# CtDPS_Stage.net
KiCad netlist of a schematic drawn in Altium Designer
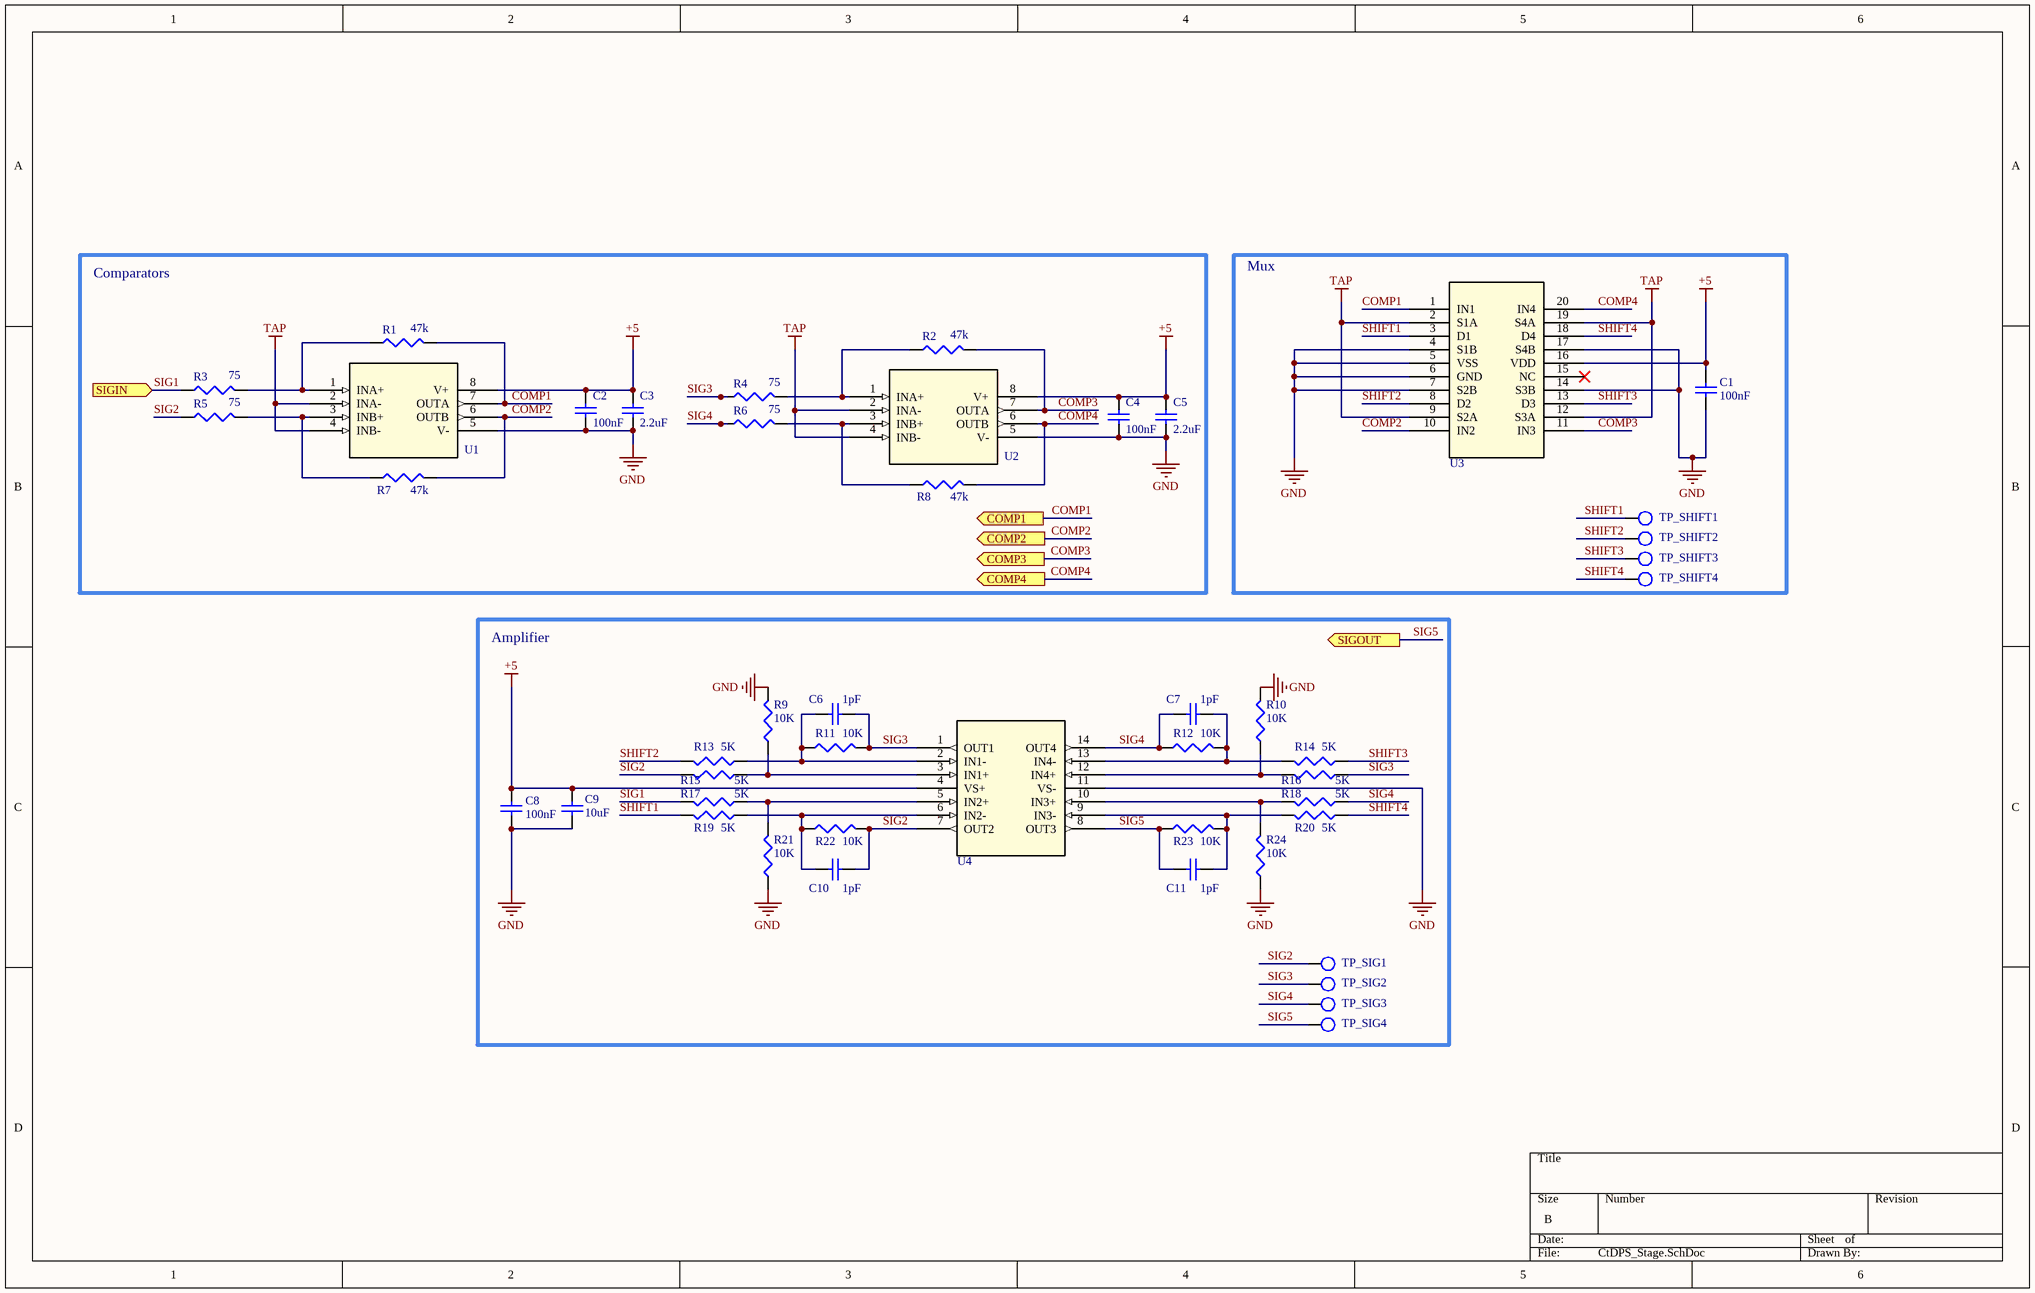
[diagram p0: CtDPS_Stage.SchDoc]

(export (version "E")
  (design (tool "Eeschema 10.0.6"))
  (components
    (comp (ref "C1")
      (value "100nF")
      (footprint "C_0402")
      (fields (field (name "LCSC PART #") "C1525"))
      (libsource (lib "ctdsp") (part "C_0402"))
    )
    (comp (ref "C2")
      (value "100nF")
      (footprint "C_0402")
      (fields (field (name "LCSC PART #") "C1525"))
      (libsource (lib "ctdsp") (part "C_0402"))
    )
    (comp (ref "C3")
      (value "2.2uF")
      (footprint "C_0402")
      (fields (field (name "LCSC PART #") "C12530"))
      (libsource (lib "ctdsp") (part "C_0402"))
    )
    (comp (ref "C4")
      (value "100nF")
      (footprint "C_0402")
      (fields (field (name "LCSC PART #") "C1525"))
      (libsource (lib "ctdsp") (part "C_0402"))
    )
    (comp (ref "C5")
      (value "2.2uF")
      (footprint "C_0402")
      (fields (field (name "LCSC PART #") "C12530"))
      (libsource (lib "ctdsp") (part "C_0402"))
    )
    (comp (ref "C6")
      (value "1pF")
      (footprint "C_0402")
      (fields (field (name "LCSC PART #") "C1550"))
      (libsource (lib "ctdsp") (part "C_0402"))
    )
    (comp (ref "C7")
      (value "1pF")
      (footprint "C_0402")
      (fields (field (name "LCSC PART #") "C1550"))
      (libsource (lib "ctdsp") (part "C_0402"))
    )
    (comp (ref "C8")
      (value "100nF")
      (footprint "C_0402")
      (fields (field (name "LCSC PART #") "C1525"))
      (libsource (lib "ctdsp") (part "C_0402"))
    )
    (comp (ref "C9")
      (value "10uF")
      (footprint "C_0402")
      (fields (field (name "LCSC PART #") "C15525"))
      (libsource (lib "ctdsp") (part "C_0402"))
    )
    (comp (ref "C10")
      (value "1pF")
      (footprint "C_0402")
      (fields (field (name "LCSC PART #") "C1550"))
      (libsource (lib "ctdsp") (part "C_0402"))
    )
    (comp (ref "C11")
      (value "1pF")
      (footprint "C_0402")
      (fields (field (name "LCSC PART #") "C1550"))
      (libsource (lib "ctdsp") (part "C_0402"))
    )
    (comp (ref "R1")
      (value "47k")
      (footprint "RES_0603")
      (fields (field (name "LCSC PART #") "C25819"))
      (libsource (lib "ctdsp") (part "RES_0603"))
    )
    (comp (ref "R2")
      (value "47k")
      (footprint "RES_0603")
      (fields (field (name "LCSC PART #") "C25819"))
      (libsource (lib "ctdsp") (part "RES_0603"))
    )
    (comp (ref "R3")
      (value "75")
      (footprint "RES_0603")
      (fields (field (name "LCSC PART #") "C4275"))
      (libsource (lib "ctdsp") (part "RES_0603"))
    )
    (comp (ref "R4")
      (value "75")
      (footprint "RES_0603")
      (fields (field (name "LCSC PART #") "C4275"))
      (libsource (lib "ctdsp") (part "RES_0603"))
    )
    (comp (ref "R5")
      (value "75")
      (footprint "RES_0603")
      (fields (field (name "LCSC PART #") "C4275"))
      (libsource (lib "ctdsp") (part "RES_0603"))
    )
    (comp (ref "R6")
      (value "75")
      (footprint "RES_0603")
      (fields (field (name "LCSC PART #") "C4275"))
      (libsource (lib "ctdsp") (part "RES_0603"))
    )
    (comp (ref "R7")
      (value "47k")
      (footprint "RES_0603")
      (fields (field (name "LCSC PART #") "C25819"))
      (libsource (lib "ctdsp") (part "RES_0603"))
    )
    (comp (ref "R8")
      (value "47k")
      (footprint "RES_0603")
      (fields (field (name "LCSC PART #") "C25819"))
      (libsource (lib "ctdsp") (part "RES_0603"))
    )
    (comp (ref "R9")
      (value "10K")
      (footprint "RES_0402")
      (fields (field (name "LCSC PART #") "C25744"))
      (libsource (lib "ctdsp") (part "RES_0402"))
    )
    (comp (ref "R10")
      (value "10K")
      (footprint "RES_0402")
      (fields (field (name "LCSC PART #") "C25744"))
      (libsource (lib "ctdsp") (part "RES_0402"))
    )
    (comp (ref "R11")
      (value "10K")
      (footprint "RES_0402")
      (fields (field (name "LCSC PART #") "C25744"))
      (libsource (lib "ctdsp") (part "RES_0402"))
    )
    (comp (ref "R12")
      (value "10K")
      (footprint "RES_0402")
      (fields (field (name "LCSC PART #") "C25744"))
      (libsource (lib "ctdsp") (part "RES_0402"))
    )
    (comp (ref "R13")
      (value "5K")
      (footprint "RES_0402")
      (fields (field (name "LCSC PART #") "C5948099"))
      (libsource (lib "ctdsp") (part "RES_0402"))
    )
    (comp (ref "R14")
      (value "5K")
      (footprint "RES_0402")
      (fields (field (name "LCSC PART #") "C5948099"))
      (libsource (lib "ctdsp") (part "RES_0402"))
    )
    (comp (ref "R15")
      (value "5K")
      (footprint "RES_0402")
      (fields (field (name "LCSC PART #") "C5948099"))
      (libsource (lib "ctdsp") (part "RES_0402"))
    )
    (comp (ref "R16")
      (value "5K")
      (footprint "RES_0402")
      (fields (field (name "LCSC PART #") "C5948099"))
      (libsource (lib "ctdsp") (part "RES_0402"))
    )
    (comp (ref "R17")
      (value "5K")
      (footprint "RES_0402")
      (fields (field (name "LCSC PART #") "C5948099"))
      (libsource (lib "ctdsp") (part "RES_0402"))
    )
    (comp (ref "R18")
      (value "5K")
      (footprint "RES_0402")
      (fields (field (name "LCSC PART #") "C5948099"))
      (libsource (lib "ctdsp") (part "RES_0402"))
    )
    (comp (ref "R19")
      (value "5K")
      (footprint "RES_0402")
      (fields (field (name "LCSC PART #") "C5948099"))
      (libsource (lib "ctdsp") (part "RES_0402"))
    )
    (comp (ref "R20")
      (value "5K")
      (footprint "RES_0402")
      (fields (field (name "LCSC PART #") "C5948099"))
      (libsource (lib "ctdsp") (part "RES_0402"))
    )
    (comp (ref "R21")
      (value "10K")
      (footprint "RES_0402")
      (fields (field (name "LCSC PART #") "C25744"))
      (libsource (lib "ctdsp") (part "RES_0402"))
    )
    (comp (ref "R22")
      (value "10K")
      (footprint "RES_0402")
      (fields (field (name "LCSC PART #") "C25744"))
      (libsource (lib "ctdsp") (part "RES_0402"))
    )
    (comp (ref "R23")
      (value "10K")
      (footprint "RES_0402")
      (fields (field (name "LCSC PART #") "C25744"))
      (libsource (lib "ctdsp") (part "RES_0402"))
    )
    (comp (ref "R24")
      (value "10K")
      (footprint "RES_0402")
      (fields (field (name "LCSC PART #") "C25744"))
      (libsource (lib "ctdsp") (part "RES_0402"))
    )
    (comp (ref "TP_SHIFT1")
      (value "TESTPOINT")
      (footprint "TESTPOINT")
      (libsource (lib "ctdsp") (part "TESTPOINT"))
    )
    (comp (ref "TP_SHIFT2")
      (value "TESTPOINT")
      (footprint "TESTPOINT")
      (libsource (lib "ctdsp") (part "TESTPOINT"))
    )
    (comp (ref "TP_SHIFT3")
      (value "TESTPOINT")
      (footprint "TESTPOINT")
      (libsource (lib "ctdsp") (part "TESTPOINT"))
    )
    (comp (ref "TP_SHIFT4")
      (value "TESTPOINT")
      (footprint "TESTPOINT")
      (libsource (lib "ctdsp") (part "TESTPOINT"))
    )
    (comp (ref "TP_SIG1")
      (value "TESTPOINT")
      (footprint "TESTPOINT")
      (libsource (lib "ctdsp") (part "TESTPOINT"))
    )
    (comp (ref "TP_SIG2")
      (value "TESTPOINT")
      (footprint "TESTPOINT")
      (libsource (lib "ctdsp") (part "TESTPOINT"))
    )
    (comp (ref "TP_SIG3")
      (value "TESTPOINT")
      (footprint "TESTPOINT")
      (libsource (lib "ctdsp") (part "TESTPOINT"))
    )
    (comp (ref "TP_SIG4")
      (value "TESTPOINT")
      (footprint "TESTPOINT")
      (libsource (lib "ctdsp") (part "TESTPOINT"))
    )
    (comp (ref "U1")
      (value "TLV3502AIDR")
      (footprint "TLV3502AIDR")
      (description "Dual 4.5ns Push-pull Rail-to-Rail Input, Rail-to-Rail Output TTL Comparators")
      (fields (field (name "LCSC PART #") "C131165"))
      (libsource (lib "ctdsp") (part "TLV3502AIDR"))
    )
    (comp (ref "U2")
      (value "TLV3502AIDR")
      (footprint "TLV3502AIDR")
      (description "Dual 4.5ns Push-pull Rail-to-Rail Input, Rail-to-Rail Output TTL Comparators")
      (fields (field (name "LCSC PART #") "C131165"))
      (libsource (lib "ctdsp") (part "TLV3502AIDR"))
    )
    (comp (ref "U3")
      (value "ADG734BRUZ-REEL")
      (footprint "ADG734BRUZ-REEL")
      (fields (field (name "LCSC PART #") "C579105"))
      (libsource (lib "ctdsp") (part "ADG734BRUZ-REEL"))
    )
    (comp (ref "U4")
      (value "ADA4891-4ARZ-R7")
      (footprint "ADA4891-4ARZ-R7")
      (description "Quad Rail-to-Rail Op-Amp, 240 MHz, 170 V/µs, SOT-23-5")
      (fields (field (name "LCSC PART #") "C654290"))
      (libsource (lib "ctdsp") (part "ADA4891-4ARZ-R7"))
    )
  )
  (nets
    (net (code "1") (name "+5") (class "Default")
      (node (ref "C1") (pin "1") (pinfunction "1_1") (pintype "passive"))
      (node (ref "C2") (pin "1") (pinfunction "1_1") (pintype "passive"))
      (node (ref "C3") (pin "2") (pinfunction "2_2") (pintype "passive"))
      (node (ref "C4") (pin "1") (pinfunction "1_1") (pintype "passive"))
      (node (ref "C5") (pin "2") (pinfunction "2_2") (pintype "passive"))
      (node (ref "C8") (pin "1") (pinfunction "1_1") (pintype "passive"))
      (node (ref "C9") (pin "2") (pinfunction "2_2") (pintype "passive"))
      (node (ref "U1") (pin "8") (pinfunction "V+_8") (pintype "power_in"))
      (node (ref "U2") (pin "8") (pinfunction "V+_8") (pintype "power_in"))
      (node (ref "U3") (pin "16") (pinfunction "VDD_16") (pintype "power_in"))
      (node (ref "U4") (pin "4") (pinfunction "VS+_4") (pintype "power_in"))
    )
    (net (code "2") (name "/COMP1") (class "Default")
      (node (ref "R1") (pin "2") (pinfunction "2_2") (pintype "passive"))
      (node (ref "U1") (pin "7") (pinfunction "OUTA_7") (pintype "output"))
      (node (ref "U3") (pin "1") (pinfunction "IN1_1") (pintype "passive"))
    )
    (net (code "3") (name "/COMP2") (class "Default")
      (node (ref "R7") (pin "2") (pinfunction "2_2") (pintype "passive"))
      (node (ref "U1") (pin "6") (pinfunction "OUTB_6") (pintype "output"))
      (node (ref "U3") (pin "10") (pinfunction "IN2_10") (pintype "passive"))
    )
    (net (code "4") (name "/COMP3") (class "Default")
      (node (ref "R2") (pin "2") (pinfunction "2_2") (pintype "passive"))
      (node (ref "U2") (pin "7") (pinfunction "OUTA_7") (pintype "output"))
      (node (ref "U3") (pin "11") (pinfunction "IN3_11") (pintype "passive"))
    )
    (net (code "5") (name "/COMP4") (class "Default")
      (node (ref "R8") (pin "2") (pinfunction "2_2") (pintype "passive"))
      (node (ref "U2") (pin "6") (pinfunction "OUTB_6") (pintype "output"))
      (node (ref "U3") (pin "20") (pinfunction "IN4_20") (pintype "passive"))
    )
    (net (code "6") (name "/SHIFT1") (class "Default")
      (node (ref "R19") (pin "1") (pinfunction "1_1") (pintype "passive"))
      (node (ref "TP_SHIFT1") (pin "1") (pinfunction "1_1") (pintype "passive"))
      (node (ref "U3") (pin "3") (pinfunction "D1_3") (pintype "passive"))
    )
    (net (code "7") (name "/SHIFT2") (class "Default")
      (node (ref "R13") (pin "1") (pinfunction "1_1") (pintype "passive"))
      (node (ref "TP_SHIFT2") (pin "1") (pinfunction "1_1") (pintype "passive"))
      (node (ref "U3") (pin "8") (pinfunction "D2_8") (pintype "passive"))
    )
    (net (code "8") (name "/SHIFT3") (class "Default")
      (node (ref "R14") (pin "2") (pinfunction "2_2") (pintype "passive"))
      (node (ref "TP_SHIFT3") (pin "1") (pinfunction "1_1") (pintype "passive"))
      (node (ref "U3") (pin "13") (pinfunction "D3_13") (pintype "passive"))
    )
    (net (code "9") (name "/SHIFT4") (class "Default")
      (node (ref "R20") (pin "2") (pinfunction "2_2") (pintype "passive"))
      (node (ref "TP_SHIFT4") (pin "1") (pinfunction "1_1") (pintype "passive"))
      (node (ref "U3") (pin "18") (pinfunction "D4_18") (pintype "passive"))
    )
    (net (code "10") (name "/SIG1") (class "Default")
      (node (ref "R17") (pin "1") (pinfunction "1_1") (pintype "passive"))
      (node (ref "R3") (pin "1") (pinfunction "1_1") (pintype "passive"))
    )
    (net (code "11") (name "/SIG2") (class "Default")
      (node (ref "C10") (pin "2") (pinfunction "2_2") (pintype "passive"))
      (node (ref "R15") (pin "1") (pinfunction "1_1") (pintype "passive"))
      (node (ref "R22") (pin "2") (pinfunction "2_2") (pintype "passive"))
      (node (ref "R5") (pin "1") (pinfunction "1_1") (pintype "passive"))
      (node (ref "TP_SIG1") (pin "1") (pinfunction "1_1") (pintype "passive"))
      (node (ref "U4") (pin "7") (pinfunction "OUT2_7") (pintype "output"))
    )
    (net (code "12") (name "/SIG3") (class "Default")
      (node (ref "C6") (pin "2") (pinfunction "2_2") (pintype "passive"))
      (node (ref "R11") (pin "2") (pinfunction "2_2") (pintype "passive"))
      (node (ref "R16") (pin "2") (pinfunction "2_2") (pintype "passive"))
      (node (ref "R4") (pin "1") (pinfunction "1_1") (pintype "passive"))
      (node (ref "TP_SIG2") (pin "1") (pinfunction "1_1") (pintype "passive"))
      (node (ref "U4") (pin "1") (pinfunction "OUT1_1") (pintype "output"))
    )
    (net (code "13") (name "/SIG4") (class "Default")
      (node (ref "C7") (pin "1") (pinfunction "1_1") (pintype "passive"))
      (node (ref "R12") (pin "1") (pinfunction "1_1") (pintype "passive"))
      (node (ref "R18") (pin "2") (pinfunction "2_2") (pintype "passive"))
      (node (ref "R6") (pin "1") (pinfunction "1_1") (pintype "passive"))
      (node (ref "TP_SIG3") (pin "1") (pinfunction "1_1") (pintype "passive"))
      (node (ref "U4") (pin "14") (pinfunction "OUT4_14") (pintype "output"))
    )
    (net (code "14") (name "/SIG5") (class "Default")
      (node (ref "C11") (pin "1") (pinfunction "1_1") (pintype "passive"))
      (node (ref "R23") (pin "1") (pinfunction "1_1") (pintype "passive"))
      (node (ref "TP_SIG4") (pin "1") (pinfunction "1_1") (pintype "passive"))
      (node (ref "U4") (pin "8") (pinfunction "OUT3_8") (pintype "output"))
    )
    (net (code "15") (name "GND") (class "Default")
      (node (ref "C1") (pin "2") (pinfunction "2_2") (pintype "passive"))
      (node (ref "C2") (pin "2") (pinfunction "2_2") (pintype "passive"))
      (node (ref "C3") (pin "1") (pinfunction "1_1") (pintype "passive"))
      (node (ref "C4") (pin "2") (pinfunction "2_2") (pintype "passive"))
      (node (ref "C5") (pin "1") (pinfunction "1_1") (pintype "passive"))
      (node (ref "C8") (pin "2") (pinfunction "2_2") (pintype "passive"))
      (node (ref "C9") (pin "1") (pinfunction "1_1") (pintype "passive"))
      (node (ref "R10") (pin "2") (pinfunction "2_2") (pintype "passive"))
      (node (ref "R21") (pin "1") (pinfunction "1_1") (pintype "passive"))
      (node (ref "R24") (pin "1") (pinfunction "1_1") (pintype "passive"))
      (node (ref "R9") (pin "2") (pinfunction "2_2") (pintype "passive"))
      (node (ref "U1") (pin "5") (pinfunction "V-_5") (pintype "power_in"))
      (node (ref "U2") (pin "5") (pinfunction "V-_5") (pintype "power_in"))
      (node (ref "U3") (pin "14") (pinfunction "S3B_14") (pintype "passive"))
      (node (ref "U3") (pin "17") (pinfunction "S4B_17") (pintype "passive"))
      (node (ref "U3") (pin "4") (pinfunction "S1B_4") (pintype "passive"))
      (node (ref "U3") (pin "5") (pinfunction "VSS_5") (pintype "power_in"))
      (node (ref "U3") (pin "6") (pinfunction "GND_6") (pintype "passive"))
      (node (ref "U3") (pin "7") (pinfunction "S2B_7") (pintype "passive"))
      (node (ref "U4") (pin "11") (pinfunction "VS-_11") (pintype "power_in"))
    )
    (net (code "16") (name "Net-(U1-INA+)") (class "Default")
      (node (ref "R1") (pin "1") (pinfunction "1_1") (pintype "passive"))
      (node (ref "R3") (pin "2") (pinfunction "2_2") (pintype "passive"))
      (node (ref "U1") (pin "1") (pinfunction "INA+_1") (pintype "input"))
    )
    (net (code "17") (name "Net-(U1-INB+)") (class "Default")
      (node (ref "R5") (pin "2") (pinfunction "2_2") (pintype "passive"))
      (node (ref "R7") (pin "1") (pinfunction "1_1") (pintype "passive"))
      (node (ref "U1") (pin "3") (pinfunction "INB+_3") (pintype "input"))
    )
    (net (code "18") (name "Net-(U2-INA+)") (class "Default")
      (node (ref "R2") (pin "1") (pinfunction "1_1") (pintype "passive"))
      (node (ref "R4") (pin "2") (pinfunction "2_2") (pintype "passive"))
      (node (ref "U2") (pin "1") (pinfunction "INA+_1") (pintype "input"))
    )
    (net (code "19") (name "Net-(U2-INB+)") (class "Default")
      (node (ref "R6") (pin "2") (pinfunction "2_2") (pintype "passive"))
      (node (ref "R8") (pin "1") (pinfunction "1_1") (pintype "passive"))
      (node (ref "U2") (pin "3") (pinfunction "INB+_3") (pintype "input"))
    )
    (net (code "20") (name "Net-(U4-IN1+)") (class "Default")
      (node (ref "R15") (pin "2") (pinfunction "2_2") (pintype "passive"))
      (node (ref "R9") (pin "1") (pinfunction "1_1") (pintype "passive"))
      (node (ref "U4") (pin "3") (pinfunction "IN1+_3") (pintype "input"))
    )
    (net (code "21") (name "Net-(U4-IN1-)") (class "Default")
      (node (ref "C6") (pin "1") (pinfunction "1_1") (pintype "passive"))
      (node (ref "R11") (pin "1") (pinfunction "1_1") (pintype "passive"))
      (node (ref "R13") (pin "2") (pinfunction "2_2") (pintype "passive"))
      (node (ref "U4") (pin "2") (pinfunction "IN1-_2") (pintype "input"))
    )
    (net (code "22") (name "Net-(U4-IN2+)") (class "Default")
      (node (ref "R17") (pin "2") (pinfunction "2_2") (pintype "passive"))
      (node (ref "R21") (pin "2") (pinfunction "2_2") (pintype "passive"))
      (node (ref "U4") (pin "5") (pinfunction "IN2+_5") (pintype "input"))
    )
    (net (code "23") (name "Net-(U4-IN2-)") (class "Default")
      (node (ref "C10") (pin "1") (pinfunction "1_1") (pintype "passive"))
      (node (ref "R19") (pin "2") (pinfunction "2_2") (pintype "passive"))
      (node (ref "R22") (pin "1") (pinfunction "1_1") (pintype "passive"))
      (node (ref "U4") (pin "6") (pinfunction "IN2-_6") (pintype "input"))
    )
    (net (code "24") (name "Net-(U4-IN3+)") (class "Default")
      (node (ref "R18") (pin "1") (pinfunction "1_1") (pintype "passive"))
      (node (ref "R24") (pin "2") (pinfunction "2_2") (pintype "passive"))
      (node (ref "U4") (pin "10") (pinfunction "IN3+_10") (pintype "input"))
    )
    (net (code "25") (name "Net-(U4-IN3-)") (class "Default")
      (node (ref "C11") (pin "2") (pinfunction "2_2") (pintype "passive"))
      (node (ref "R20") (pin "1") (pinfunction "1_1") (pintype "passive"))
      (node (ref "R23") (pin "2") (pinfunction "2_2") (pintype "passive"))
      (node (ref "U4") (pin "9") (pinfunction "IN3-_9") (pintype "input"))
    )
    (net (code "26") (name "Net-(U4-IN4+)") (class "Default")
      (node (ref "R10") (pin "1") (pinfunction "1_1") (pintype "passive"))
      (node (ref "R16") (pin "1") (pinfunction "1_1") (pintype "passive"))
      (node (ref "U4") (pin "12") (pinfunction "IN4+_12") (pintype "input"))
    )
    (net (code "27") (name "Net-(U4-IN4-)") (class "Default")
      (node (ref "C7") (pin "2") (pinfunction "2_2") (pintype "passive"))
      (node (ref "R12") (pin "2") (pinfunction "2_2") (pintype "passive"))
      (node (ref "R14") (pin "1") (pinfunction "1_1") (pintype "passive"))
      (node (ref "U4") (pin "13") (pinfunction "IN4-_13") (pintype "input"))
    )
    (net (code "28") (name "TAP") (class "Default")
      (node (ref "U1") (pin "2") (pinfunction "INA-_2") (pintype "input"))
      (node (ref "U1") (pin "4") (pinfunction "INB-_4") (pintype "input"))
      (node (ref "U2") (pin "2") (pinfunction "INA-_2") (pintype "input"))
      (node (ref "U2") (pin "4") (pinfunction "INB-_4") (pintype "input"))
      (node (ref "U3") (pin "12") (pinfunction "S3A_12") (pintype "passive"))
      (node (ref "U3") (pin "19") (pinfunction "S4A_19") (pintype "passive"))
      (node (ref "U3") (pin "2") (pinfunction "S1A_2") (pintype "passive"))
      (node (ref "U3") (pin "9") (pinfunction "S2A_9") (pintype "passive"))
    )
    (net (code "29") (name "unconnected-(U3-NC-Pad15)") (class "Default")
      (node (ref "U3") (pin "15") (pinfunction "NC_15") (pintype "passive+no_connect"))
    )
  )
)
